# VESC_POWER_SCH.net
KiCad netlist of a schematic drawn in Altium Designer
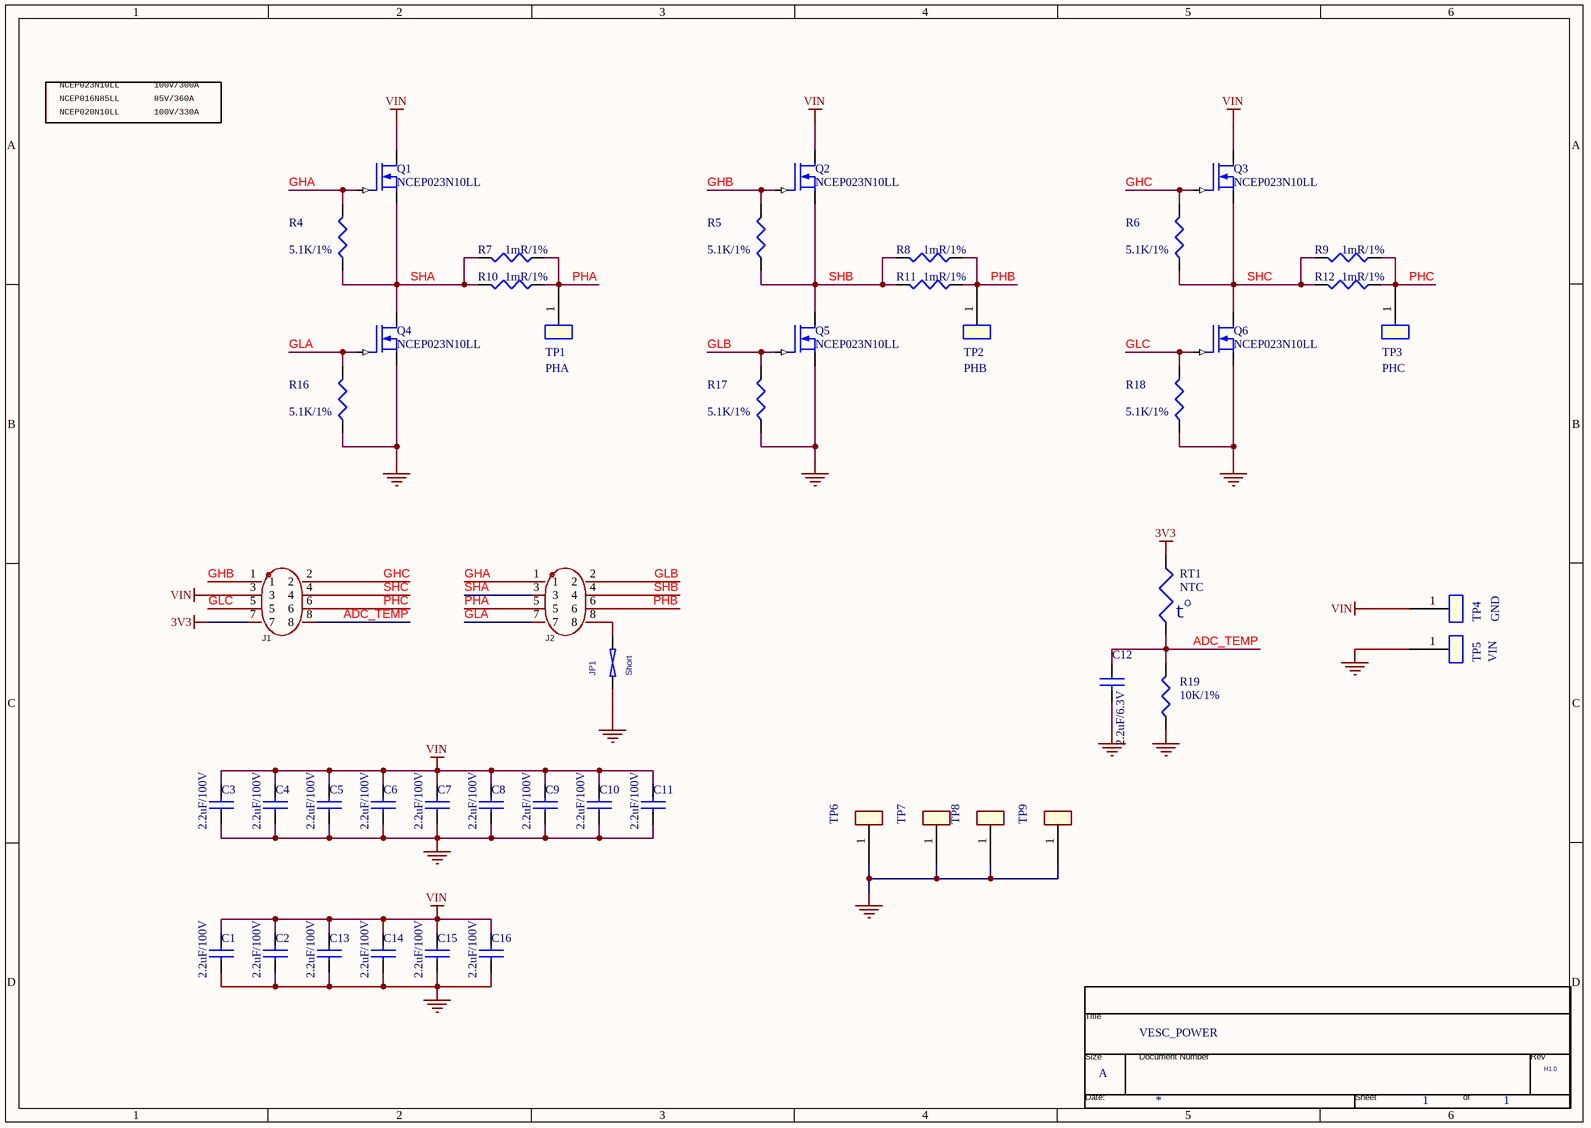
[diagram p0: VESC_POWER_SCH.SchDoc]

(export (version "E")
  (design (tool "Eeschema 10.0.6"))
  (components
    (comp (ref "*")
      (value "TitleBlock0")
      (fields
        (field (name "REVCODE") "H1.0")
        (field (name "TITLE") "VESC_POWER")
        (field (name "PAGE SIZE") "A")
        (field (name "PAGE NUMBER") "1")
        (field (name "PAGE COUNT") "1")
      )
      (libsource (lib "*") (part "TitleBlock0"))
    )
    (comp (ref "C1") (value "2.2uF/100V") (footprint "CAPC3225X230N") (libsource (lib "*") (part "CAP NP")))
    (comp (ref "C2") (value "2.2uF/100V") (footprint "CAPC3225X230N") (libsource (lib "*") (part "CAP NP")))
    (comp (ref "C3") (value "2.2uF/100V") (footprint "CAPC3225X230N") (libsource (lib "*") (part "CAP NP")))
    (comp (ref "C4") (value "2.2uF/100V") (footprint "CAPC3225X230N") (libsource (lib "*") (part "CAP NP")))
    (comp (ref "C5") (value "2.2uF/100V") (footprint "CAPC3225X230N") (libsource (lib "*") (part "CAP NP")))
    (comp (ref "C6") (value "2.2uF/100V") (footprint "CAPC3225X230N") (libsource (lib "*") (part "CAP NP")))
    (comp (ref "C7") (value "2.2uF/100V") (footprint "CAPC3225X230N") (libsource (lib "*") (part "CAP NP")))
    (comp (ref "C8") (value "2.2uF/100V") (footprint "CAPC3225X230N") (libsource (lib "*") (part "CAP NP")))
    (comp (ref "C9") (value "2.2uF/100V") (footprint "CAPC3225X230N") (libsource (lib "*") (part "CAP NP")))
    (comp (ref "C10") (value "2.2uF/100V") (footprint "CAPC3225X230N") (libsource (lib "*") (part "CAP NP")))
    (comp (ref "C11") (value "2.2uF/100V") (footprint "CAPC3225X230N") (libsource (lib "*") (part "CAP NP")))
    (comp (ref "C12") (value "2.2uF/6.3V") (footprint "C0603") (libsource (lib "*") (part "CAP NP")))
    (comp (ref "C13") (value "2.2uF/100V") (footprint "CAPC3225X230N") (libsource (lib "*") (part "CAP NP")))
    (comp (ref "C14") (value "2.2uF/100V") (footprint "CAPC3225X230N") (libsource (lib "*") (part "CAP NP")))
    (comp (ref "C15") (value "2.2uF/100V") (footprint "CAPC3225X230N") (libsource (lib "*") (part "CAP NP")))
    (comp (ref "C16") (value "2.2uF/100V") (footprint "CAPC3225X230N") (libsource (lib "*") (part "CAP NP")))
    (comp (ref "J1")
      (value "X6521WVS-2x04H-C60D74")
      (footprint "HDR-SMD_8P-P1.27-V-M-C2-C4-LS5.3")
      (fields (field (name "MANUFACTURER") "XKB Connection(中国星坤)"))
      (libsource (lib "VESC_POWER_Library") (part "X6521WVS-2x04H-C60D74"))
    )
    (comp (ref "J2")
      (value "X6521WVS-2x04H-C60D74")
      (footprint "HDR-SMD_8P-P1.27-V-M-C2-C4-LS5.3")
      (fields (field (name "MANUFACTURER") "XKB Connection(中国星坤)"))
      (libsource (lib "VESC_POWER_Library") (part "X6521WVS-2x04H-C60D74"))
    )
    (comp (ref "JP1")
      (value "Short")
      (footprint "SHORT")
      (description "2 PIN SHORTED TO CONNECT DIFFERENT NETS")
      (fields (field (name "PART_NUMBER") "TMP-442"))
      (libsource (lib "VESC_POWER_Library") (part "SHORT"))
    )
    (comp (ref "Q1") (value "NCEP023N10LL") (footprint "TOLL") (libsource (lib "*") (part "MOSFET N")))
    (comp (ref "Q2") (value "NCEP023N10LL") (footprint "TOLL") (libsource (lib "*") (part "MOSFET N")))
    (comp (ref "Q3") (value "NCEP023N10LL") (footprint "TOLL") (libsource (lib "*") (part "MOSFET N")))
    (comp (ref "Q4") (value "NCEP023N10LL") (footprint "TOLL") (libsource (lib "*") (part "MOSFET N")))
    (comp (ref "Q5") (value "NCEP023N10LL") (footprint "TOLL") (libsource (lib "*") (part "MOSFET N")))
    (comp (ref "Q6") (value "NCEP023N10LL") (footprint "TOLL") (libsource (lib "*") (part "MOSFET N")))
    (comp (ref "R4") (value "5.1K/1%") (footprint "R0603") (libsource (lib "*") (part "RESISTOR")))
    (comp (ref "R5") (value "5.1K/1%") (footprint "R0603") (libsource (lib "*") (part "RESISTOR")))
    (comp (ref "R6") (value "5.1K/1%") (footprint "R0603") (libsource (lib "*") (part "RESISTOR")))
    (comp (ref "R7") (value "1mR/1%") (footprint "R3920") (libsource (lib "*") (part "RESISTOR")))
    (comp (ref "R8") (value "1mR/1%") (footprint "R3920") (libsource (lib "*") (part "RESISTOR")))
    (comp (ref "R9") (value "1mR/1%") (footprint "R3920") (libsource (lib "*") (part "RESISTOR")))
    (comp (ref "R10") (value "1mR/1%") (footprint "R3920") (libsource (lib "*") (part "RESISTOR")))
    (comp (ref "R11") (value "1mR/1%") (footprint "R3920") (libsource (lib "*") (part "RESISTOR")))
    (comp (ref "R12") (value "1mR/1%") (footprint "R3920") (libsource (lib "*") (part "RESISTOR")))
    (comp (ref "R16") (value "5.1K/1%") (footprint "R0603") (libsource (lib "*") (part "RESISTOR")))
    (comp (ref "R17") (value "5.1K/1%") (footprint "R0603") (libsource (lib "*") (part "RESISTOR")))
    (comp (ref "R18") (value "5.1K/1%") (footprint "R0603") (libsource (lib "*") (part "RESISTOR")))
    (comp (ref "R19") (value "10K/1%") (footprint "R0603") (libsource (lib "*") (part "RESISTOR")))
    (comp (ref "RT1") (value "NTC") (footprint "R0603") (libsource (lib "*") (part "NTC")))
    (comp (ref "TP1") (value "PHA") (footprint "TP_8x8") (libsource (lib "") (part "TEST POINT_1")))
    (comp (ref "TP2") (value "PHB") (footprint "TP_8x8") (libsource (lib "") (part "TEST POINT_1")))
    (comp (ref "TP3") (value "PHC") (footprint "TP_8x8") (libsource (lib "") (part "TEST POINT_1")))
    (comp (ref "TP4") (value "GND") (footprint "TP_8x8") (libsource (lib "*") (part "TEST POINT")))
    (comp (ref "TP5") (value "VIN") (footprint "TP_8x8") (libsource (lib "*") (part "TEST POINT")))
    (comp (ref "TP6")
      (value "TEST POINT")
      (footprint "HOLE-3.2MM_M")
      (libsource (lib "VESC_POWER_Library") (part "TEST POINT"))
    )
    (comp (ref "TP7")
      (value "TEST POINT")
      (footprint "HOLE-3.2MM_M")
      (libsource (lib "VESC_POWER_Library") (part "TEST POINT"))
    )
    (comp (ref "TP8")
      (value "TEST POINT")
      (footprint "HOLE-3.2MM_M")
      (libsource (lib "VESC_POWER_Library") (part "TEST POINT"))
    )
    (comp (ref "TP9")
      (value "TEST POINT")
      (footprint "HOLE-3.2MM_M")
      (libsource (lib "VESC_POWER_Library") (part "TEST POINT"))
    )
  )
  (nets
    (net (code "1") (name "/ADC_TEMP") (class "Default")
      (node (ref "C12") (pin "1") (pinfunction "1_1") (pintype "passive"))
      (node (ref "J1") (pin "8") (pinfunction "8_8") (pintype "passive"))
      (node (ref "R19") (pin "2") (pinfunction "2_2") (pintype "passive"))
      (node (ref "RT1") (pin "2") (pinfunction "2_2") (pintype "passive"))
    )
    (net (code "2") (name "/GHA") (class "Default")
      (node (ref "J2") (pin "1") (pinfunction "1_1") (pintype "passive"))
      (node (ref "Q1") (pin "1") (pinfunction "GATE_1") (pintype "input"))
      (node (ref "R4") (pin "2") (pinfunction "2_2") (pintype "passive"))
    )
    (net (code "3") (name "/GHB") (class "Default")
      (node (ref "J1") (pin "1") (pinfunction "1_1") (pintype "passive"))
      (node (ref "Q2") (pin "1") (pinfunction "GATE_1") (pintype "input"))
      (node (ref "R5") (pin "2") (pinfunction "2_2") (pintype "passive"))
    )
    (net (code "4") (name "/GHC") (class "Default")
      (node (ref "J1") (pin "2") (pinfunction "2_2") (pintype "passive"))
      (node (ref "Q3") (pin "1") (pinfunction "GATE_1") (pintype "input"))
      (node (ref "R6") (pin "2") (pinfunction "2_2") (pintype "passive"))
    )
    (net (code "5") (name "/GLA") (class "Default")
      (node (ref "J2") (pin "7") (pinfunction "7_7") (pintype "passive"))
      (node (ref "Q4") (pin "1") (pinfunction "GATE_1") (pintype "input"))
      (node (ref "R16") (pin "2") (pinfunction "2_2") (pintype "passive"))
    )
    (net (code "6") (name "/GLB") (class "Default")
      (node (ref "J2") (pin "2") (pinfunction "2_2") (pintype "passive"))
      (node (ref "Q5") (pin "1") (pinfunction "GATE_1") (pintype "input"))
      (node (ref "R17") (pin "2") (pinfunction "2_2") (pintype "passive"))
    )
    (net (code "7") (name "/GLC") (class "Default")
      (node (ref "J1") (pin "5") (pinfunction "5_5") (pintype "passive"))
      (node (ref "Q6") (pin "1") (pinfunction "GATE_1") (pintype "input"))
      (node (ref "R18") (pin "2") (pinfunction "2_2") (pintype "passive"))
    )
    (net (code "8") (name "/PHA") (class "Default")
      (node (ref "J2") (pin "5") (pinfunction "5_5") (pintype "passive"))
      (node (ref "R10") (pin "1") (pinfunction "1_1") (pintype "passive"))
      (node (ref "R7") (pin "1") (pinfunction "1_1") (pintype "passive"))
      (node (ref "TP1") (pin "1") (pinfunction "1_1") (pintype "passive"))
    )
    (net (code "9") (name "/PHB") (class "Default")
      (node (ref "J2") (pin "6") (pinfunction "6_6") (pintype "passive"))
      (node (ref "R11") (pin "1") (pinfunction "1_1") (pintype "passive"))
      (node (ref "R8") (pin "1") (pinfunction "1_1") (pintype "passive"))
      (node (ref "TP2") (pin "1") (pinfunction "1_1") (pintype "passive"))
    )
    (net (code "10") (name "/PHC") (class "Default")
      (node (ref "J1") (pin "6") (pinfunction "6_6") (pintype "passive"))
      (node (ref "R12") (pin "1") (pinfunction "1_1") (pintype "passive"))
      (node (ref "R9") (pin "1") (pinfunction "1_1") (pintype "passive"))
      (node (ref "TP3") (pin "1") (pinfunction "1_1") (pintype "passive"))
    )
    (net (code "11") (name "/SHA") (class "Default")
      (node (ref "J2") (pin "3") (pinfunction "3_3") (pintype "passive"))
      (node (ref "Q1") (pin "3") (pinfunction "SOURCE_3") (pintype "passive"))
      (node (ref "Q4") (pin "2") (pinfunction "DRAIN_2") (pintype "passive"))
      (node (ref "R10") (pin "2") (pinfunction "2_2") (pintype "passive"))
      (node (ref "R4") (pin "1") (pinfunction "1_1") (pintype "passive"))
      (node (ref "R7") (pin "2") (pinfunction "2_2") (pintype "passive"))
    )
    (net (code "12") (name "/SHB") (class "Default")
      (node (ref "J2") (pin "4") (pinfunction "4_4") (pintype "passive"))
      (node (ref "Q2") (pin "3") (pinfunction "SOURCE_3") (pintype "passive"))
      (node (ref "Q5") (pin "2") (pinfunction "DRAIN_2") (pintype "passive"))
      (node (ref "R11") (pin "2") (pinfunction "2_2") (pintype "passive"))
      (node (ref "R5") (pin "1") (pinfunction "1_1") (pintype "passive"))
      (node (ref "R8") (pin "2") (pinfunction "2_2") (pintype "passive"))
    )
    (net (code "13") (name "/SHC") (class "Default")
      (node (ref "J1") (pin "4") (pinfunction "4_4") (pintype "passive"))
      (node (ref "Q3") (pin "3") (pinfunction "SOURCE_3") (pintype "passive"))
      (node (ref "Q6") (pin "2") (pinfunction "DRAIN_2") (pintype "passive"))
      (node (ref "R12") (pin "2") (pinfunction "2_2") (pintype "passive"))
      (node (ref "R6") (pin "1") (pinfunction "1_1") (pintype "passive"))
      (node (ref "R9") (pin "2") (pinfunction "2_2") (pintype "passive"))
    )
    (net (code "14") (name "3V3") (class "Default")
      (node (ref "J1") (pin "7") (pinfunction "7_7") (pintype "passive"))
      (node (ref "RT1") (pin "1") (pinfunction "1_1") (pintype "passive"))
    )
    (net (code "15") (name "GND") (class "Default")
      (node (ref "C1") (pin "1") (pinfunction "1_1") (pintype "passive"))
      (node (ref "C10") (pin "1") (pinfunction "1_1") (pintype "passive"))
      (node (ref "C11") (pin "1") (pinfunction "1_1") (pintype "passive"))
      (node (ref "C12") (pin "2") (pinfunction "2_2") (pintype "passive"))
      (node (ref "C13") (pin "1") (pinfunction "1_1") (pintype "passive"))
      (node (ref "C14") (pin "1") (pinfunction "1_1") (pintype "passive"))
      (node (ref "C15") (pin "1") (pinfunction "1_1") (pintype "passive"))
      (node (ref "C16") (pin "1") (pinfunction "1_1") (pintype "passive"))
      (node (ref "C2") (pin "1") (pinfunction "1_1") (pintype "passive"))
      (node (ref "C3") (pin "1") (pinfunction "1_1") (pintype "passive"))
      (node (ref "C4") (pin "1") (pinfunction "1_1") (pintype "passive"))
      (node (ref "C5") (pin "1") (pinfunction "1_1") (pintype "passive"))
      (node (ref "C6") (pin "1") (pinfunction "1_1") (pintype "passive"))
      (node (ref "C7") (pin "1") (pinfunction "1_1") (pintype "passive"))
      (node (ref "C8") (pin "1") (pinfunction "1_1") (pintype "passive"))
      (node (ref "C9") (pin "1") (pinfunction "1_1") (pintype "passive"))
      (node (ref "JP1") (pin "1") (pinfunction "1_1") (pintype "passive"))
      (node (ref "Q4") (pin "3") (pinfunction "SOURCE_3") (pintype "passive"))
      (node (ref "Q5") (pin "3") (pinfunction "SOURCE_3") (pintype "passive"))
      (node (ref "Q6") (pin "3") (pinfunction "SOURCE_3") (pintype "passive"))
      (node (ref "R16") (pin "1") (pinfunction "1_1") (pintype "passive"))
      (node (ref "R17") (pin "1") (pinfunction "1_1") (pintype "passive"))
      (node (ref "R18") (pin "1") (pinfunction "1_1") (pintype "passive"))
      (node (ref "R19") (pin "1") (pinfunction "1_1") (pintype "passive"))
      (node (ref "TP5") (pin "1") (pinfunction "1_1") (pintype "passive"))
      (node (ref "TP6") (pin "1") (pinfunction "1_1") (pintype "passive"))
      (node (ref "TP7") (pin "1") (pinfunction "1_1") (pintype "passive"))
      (node (ref "TP8") (pin "1") (pinfunction "1_1") (pintype "passive"))
      (node (ref "TP9") (pin "1") (pinfunction "1_1") (pintype "passive"))
    )
    (net (code "16") (name "Net-(J2-Pad8)") (class "Default")
      (node (ref "J2") (pin "8") (pinfunction "8_8") (pintype "passive"))
      (node (ref "JP1") (pin "2") (pinfunction "2_2") (pintype "passive"))
    )
    (net (code "17") (name "VIN") (class "Default")
      (node (ref "C1") (pin "2") (pinfunction "2_2") (pintype "passive"))
      (node (ref "C10") (pin "2") (pinfunction "2_2") (pintype "passive"))
      (node (ref "C11") (pin "2") (pinfunction "2_2") (pintype "passive"))
      (node (ref "C13") (pin "2") (pinfunction "2_2") (pintype "passive"))
      (node (ref "C14") (pin "2") (pinfunction "2_2") (pintype "passive"))
      (node (ref "C15") (pin "2") (pinfunction "2_2") (pintype "passive"))
      (node (ref "C16") (pin "2") (pinfunction "2_2") (pintype "passive"))
      (node (ref "C2") (pin "2") (pinfunction "2_2") (pintype "passive"))
      (node (ref "C3") (pin "2") (pinfunction "2_2") (pintype "passive"))
      (node (ref "C4") (pin "2") (pinfunction "2_2") (pintype "passive"))
      (node (ref "C5") (pin "2") (pinfunction "2_2") (pintype "passive"))
      (node (ref "C6") (pin "2") (pinfunction "2_2") (pintype "passive"))
      (node (ref "C7") (pin "2") (pinfunction "2_2") (pintype "passive"))
      (node (ref "C8") (pin "2") (pinfunction "2_2") (pintype "passive"))
      (node (ref "C9") (pin "2") (pinfunction "2_2") (pintype "passive"))
      (node (ref "J1") (pin "3") (pinfunction "3_3") (pintype "passive"))
      (node (ref "Q1") (pin "2") (pinfunction "DRAIN_2") (pintype "passive"))
      (node (ref "Q2") (pin "2") (pinfunction "DRAIN_2") (pintype "passive"))
      (node (ref "Q3") (pin "2") (pinfunction "DRAIN_2") (pintype "passive"))
      (node (ref "TP4") (pin "1") (pinfunction "1_1") (pintype "passive"))
    )
  )
)
